# dremel.net
KiCad netlist of a schematic drawn in EAGLE
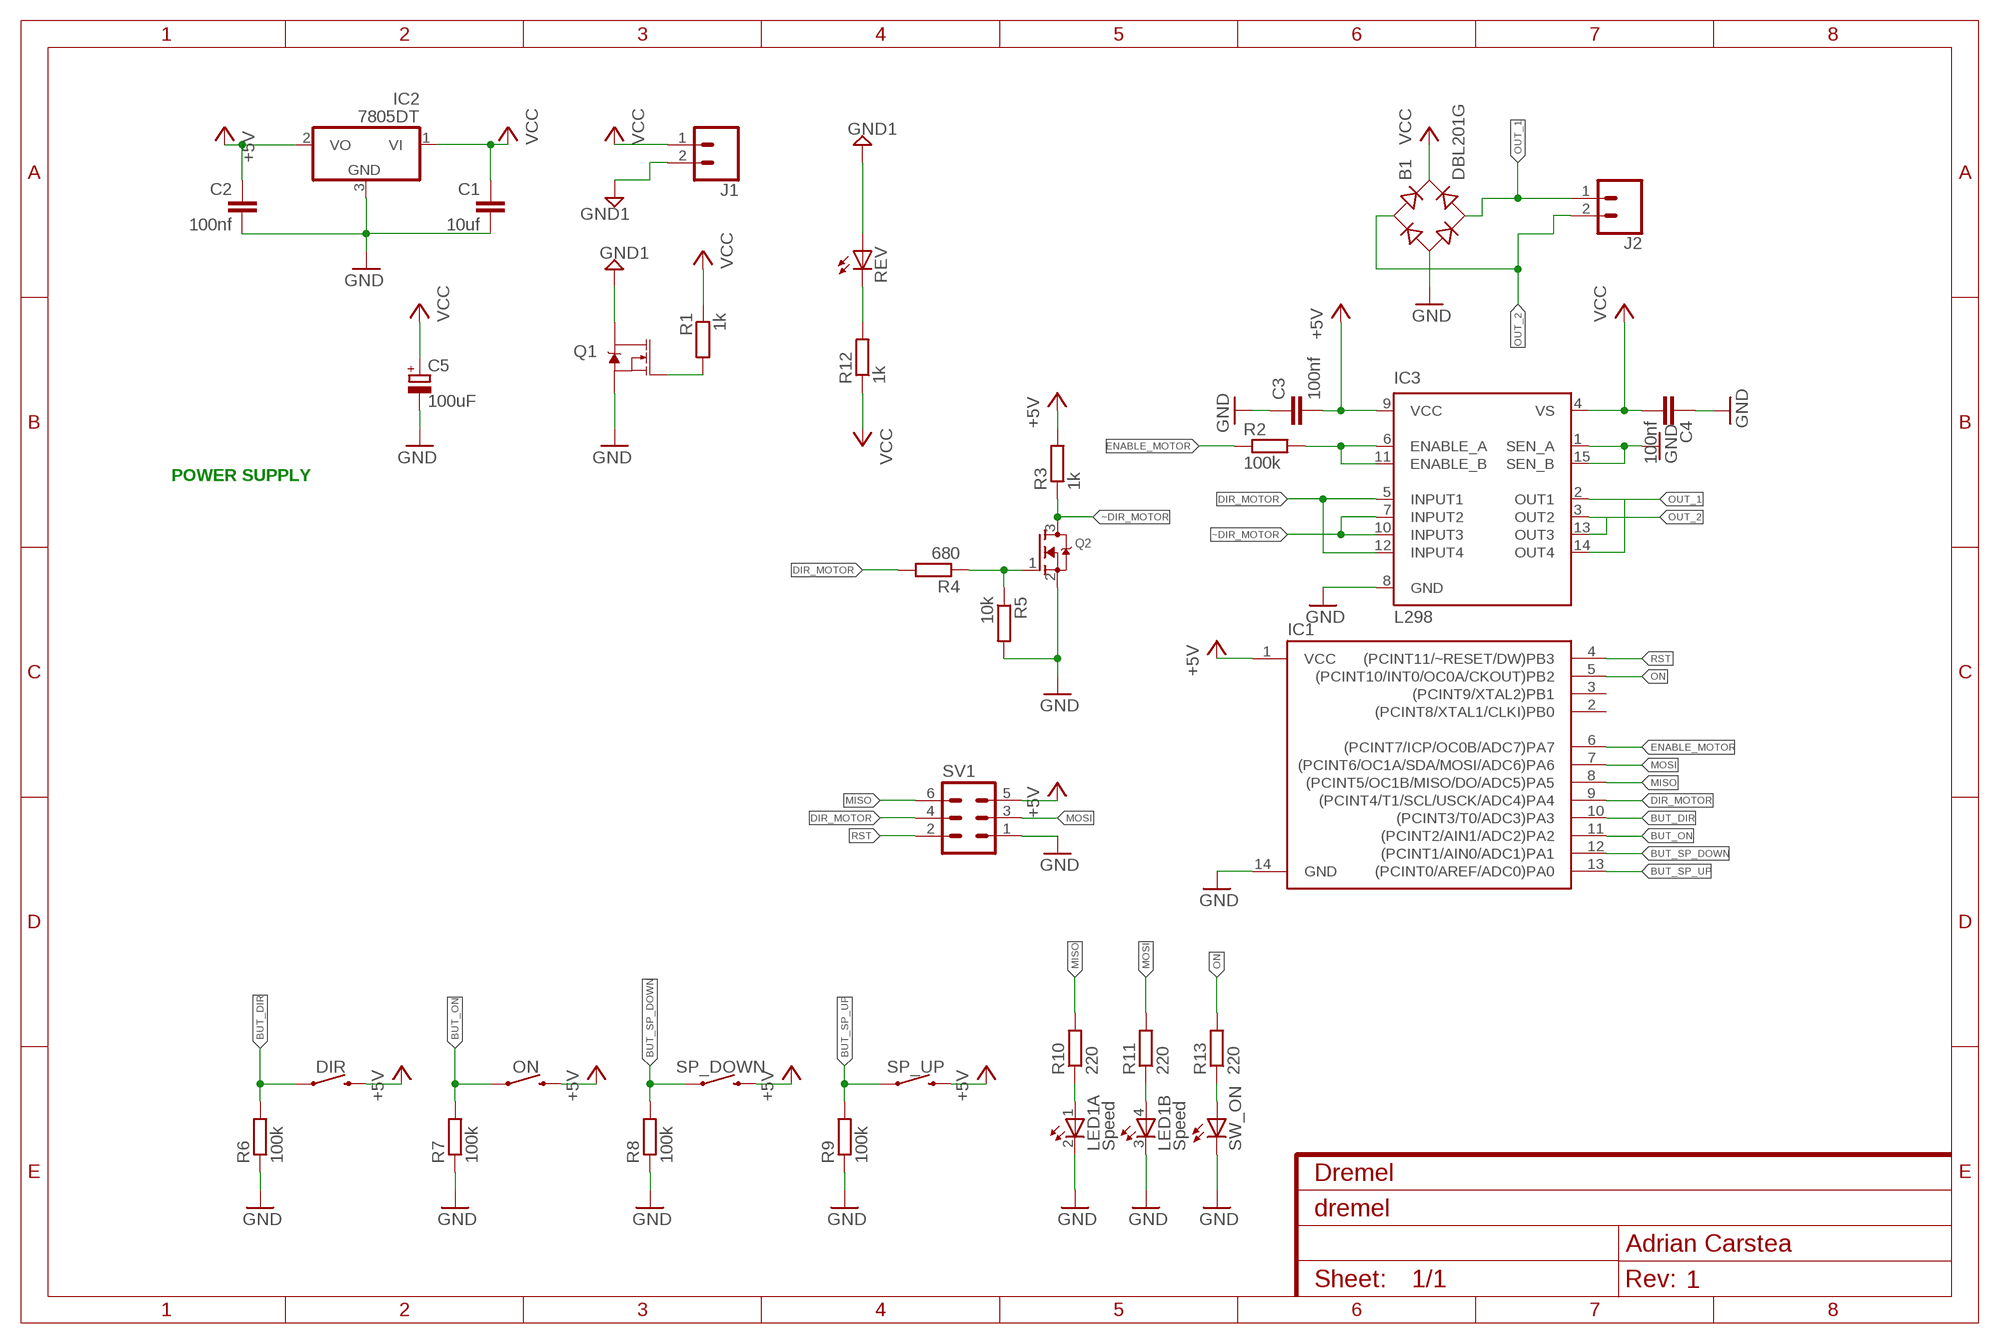
[diagram p0: schematic, sheet 1]

(export (version "E")
  (design (tool "Eeschema 10.0.6"))
  (components
    (comp (ref "B1")
      (value "DBL201G")
      (footprint "eagle-import:DB")
      (libsource (lib "eagle-import") (part "DB?GL201"))
    )
    (comp (ref "C1")
      (value "10uf")
      (footprint "eagle-import:C1206")
      (libsource (lib "eagle-import") (part "C-EUC1206"))
    )
    (comp (ref "C2")
      (value "100nf")
      (footprint "eagle-import:C1206")
      (libsource (lib "eagle-import") (part "C-EUC1206"))
    )
    (comp (ref "C3")
      (value "100nf")
      (footprint "eagle-import:C1206")
      (libsource (lib "eagle-import") (part "C-EUC1206"))
    )
    (comp (ref "C4")
      (value "100nf")
      (footprint "eagle-import:C1206")
      (libsource (lib "eagle-import") (part "C-EUC1206"))
    )
    (comp (ref "C5")
      (value "100uF")
      (footprint "eagle-import:E5-10,5")
      (libsource (lib "eagle-import") (part "CPOL-EUE5-10.5"))
    )
    (comp (ref "DIR")
      (value "MOMENTARY-SWITCH-SPST-SMD-5.2MM")
      (footprint "eagle-import:TACTILE_SWITCH_SMD_5.2MM")
      (libsource (lib "eagle-import") (part "MOMENTARY-SWITCH-SPST-SMD-5.2MM"))
    )
    (comp (ref "IC1")
      (value "ATTINY84ATTINY84-20PU")
      (footprint "eagle-import:DIP14")
      (libsource (lib "eagle-import") (part "ATTINY84ATTINY84-20PU"))
    )
    (comp (ref "IC2")
      (value "7805DT")
      (footprint "eagle-import:TO252")
      (libsource (lib "eagle-import") (part "78DT05"))
    )
    (comp (ref "IC3")
      (value "L298")
      (footprint "eagle-import:MULTIWATT-15")
      (fields (field (name "MPN") "L298N"))
      (libsource (lib "eagle-import") (part "L298"))
    )
    (comp (ref "J1")
      (value "CONN_025MM")
      (footprint "eagle-import:SCREWTERMINAL-5MM-2")
      (libsource (lib "eagle-import") (part "CONN_025MM"))
    )
    (comp (ref "J2")
      (value "CONN_025MM")
      (footprint "eagle-import:SCREWTERMINAL-5MM-2")
      (libsource (lib "eagle-import") (part "CONN_025MM"))
    )
    (comp (ref "LED1")
      (value "Speed")
      (footprint "eagle-import:P-LCC-4_2")
      (libsource (lib "eagle-import") (part "TOPLED-2-/"))
    )
    (comp (ref "ON")
      (value "MOMENTARY-SWITCH-SPST-SMD-5.2MM")
      (footprint "eagle-import:TACTILE_SWITCH_SMD_5.2MM")
      (libsource (lib "eagle-import") (part "MOMENTARY-SWITCH-SPST-SMD-5.2MM"))
    )
    (comp (ref "Q1")
      (value "MOSFET-NCH-FDD8780")
      (footprint "eagle-import:DPAK")
      (libsource (lib "eagle-import") (part "MOSFET-NCH-FDD8780"))
    )
    (comp (ref "Q2")
      (value "MOSFET-NREFLOW")
      (footprint "eagle-import:SOT23")
      (libsource (lib "eagle-import") (part "MOSFET-NREFLOW"))
    )
    (comp (ref "R1")
      (value "1k")
      (footprint "eagle-import:R0805")
      (libsource (lib "eagle-import") (part "R-EU_R0805"))
    )
    (comp (ref "R2")
      (value "100k")
      (footprint "eagle-import:M0805")
      (libsource (lib "eagle-import") (part "R-EU_M0805"))
    )
    (comp (ref "R3")
      (value "1k")
      (footprint "eagle-import:M0805")
      (libsource (lib "eagle-import") (part "R-EU_M0805"))
    )
    (comp (ref "R4")
      (value "680")
      (footprint "eagle-import:M0805")
      (libsource (lib "eagle-import") (part "R-EU_M0805"))
    )
    (comp (ref "R5")
      (value "10k")
      (footprint "eagle-import:M0805")
      (libsource (lib "eagle-import") (part "R-EU_M0805"))
    )
    (comp (ref "R6")
      (value "100k")
      (footprint "eagle-import:M0805")
      (libsource (lib "eagle-import") (part "R-EU_M0805"))
    )
    (comp (ref "R7")
      (value "100k")
      (footprint "eagle-import:M0805")
      (libsource (lib "eagle-import") (part "R-EU_M0805"))
    )
    (comp (ref "R8")
      (value "100k")
      (footprint "eagle-import:M0805")
      (libsource (lib "eagle-import") (part "R-EU_M0805"))
    )
    (comp (ref "R9")
      (value "100k")
      (footprint "eagle-import:M0805")
      (libsource (lib "eagle-import") (part "R-EU_M0805"))
    )
    (comp (ref "R10")
      (value "220")
      (footprint "eagle-import:M0805")
      (libsource (lib "eagle-import") (part "R-EU_M0805"))
    )
    (comp (ref "R11")
      (value "220")
      (footprint "eagle-import:M0805")
      (libsource (lib "eagle-import") (part "R-EU_M0805"))
    )
    (comp (ref "R12")
      (value "1k")
      (footprint "eagle-import:M0805")
      (libsource (lib "eagle-import") (part "R-EU_M0805"))
    )
    (comp (ref "R13")
      (value "220")
      (footprint "eagle-import:M0805")
      (libsource (lib "eagle-import") (part "R-EU_M0805"))
    )
    (comp (ref "REV")
      (value "LEDSML0805")
      (footprint "eagle-import:SML0805")
      (libsource (lib "eagle-import") (part "LEDSML0805"))
    )
    (comp (ref "SP_DOWN")
      (value "MOMENTARY-SWITCH-SPST-SMD-5.2MM")
      (footprint "eagle-import:TACTILE_SWITCH_SMD_5.2MM")
      (libsource (lib "eagle-import") (part "MOMENTARY-SWITCH-SPST-SMD-5.2MM"))
    )
    (comp (ref "SP_UP")
      (value "MOMENTARY-SWITCH-SPST-SMD-5.2MM")
      (footprint "eagle-import:TACTILE_SWITCH_SMD_5.2MM")
      (libsource (lib "eagle-import") (part "MOMENTARY-SWITCH-SPST-SMD-5.2MM"))
    )
    (comp (ref "SV1")
      (value "MA03-2")
      (footprint "eagle-import:MA03-2")
      (libsource (lib "eagle-import") (part "MA03-2"))
    )
    (comp (ref "SW_ON")
      (value "LEDSML0805")
      (footprint "eagle-import:SML0805")
      (libsource (lib "eagle-import") (part "LEDSML0805"))
    )
  )
  (nets
    (net (code "1") (name "+5V") (class "Default")
      (node (ref "C2") (pin "1") (pinfunction "1_1") (pintype "passive"))
      (node (ref "C3") (pin "2") (pinfunction "2_2") (pintype "passive"))
      (node (ref "DIR") (pin "3") (pinfunction "2_3") (pintype "passive"))
      (node (ref "IC1") (pin "1") (pinfunction "VCC_1") (pintype "bidirectional"))
      (node (ref "IC2") (pin "2") (pinfunction "VO_2") (pintype "passive"))
      (node (ref "IC3") (pin "9") (pinfunction "VCC_9") (pintype "power_in"))
      (node (ref "ON") (pin "3") (pinfunction "2_3") (pintype "passive"))
      (node (ref "R3") (pin "2") (pinfunction "2_2") (pintype "passive"))
      (node (ref "SP_DOWN") (pin "3") (pinfunction "2_3") (pintype "passive"))
      (node (ref "SP_UP") (pin "3") (pinfunction "2_3") (pintype "passive"))
      (node (ref "SV1") (pin "5") (pinfunction "5_5") (pintype "passive"))
    )
    (net (code "2") (name "/~{DIR_MOTOR}") (class "Default")
      (node (ref "IC3") (pin "10") (pinfunction "INPUT3_10") (pintype "input"))
      (node (ref "IC3") (pin "7") (pinfunction "INPUT2_7") (pintype "input"))
      (node (ref "Q2") (pin "3") (pinfunction "D_3") (pintype "bidirectional"))
      (node (ref "R3") (pin "1") (pinfunction "1_1") (pintype "passive"))
    )
    (net (code "3") (name "BUT_DIR") (class "Default")
      (node (ref "DIR") (pin "1") (pinfunction "1_1") (pintype "passive"))
      (node (ref "IC1") (pin "10") (pinfunction "(PCINT3/T0/ADC3)PA3_10") (pintype "bidirectional"))
      (node (ref "R6") (pin "2") (pinfunction "2_2") (pintype "passive"))
    )
    (net (code "4") (name "BUT_ON") (class "Default")
      (node (ref "IC1") (pin "11") (pinfunction "(PCINT2/AIN1/ADC2)PA2_11") (pintype "bidirectional"))
      (node (ref "ON") (pin "1") (pinfunction "1_1") (pintype "passive"))
      (node (ref "R7") (pin "2") (pinfunction "2_2") (pintype "passive"))
    )
    (net (code "5") (name "BUT_SP_DOWN") (class "Default")
      (node (ref "IC1") (pin "12") (pinfunction "(PCINT1/AIN0/ADC1)PA1_12") (pintype "bidirectional"))
      (node (ref "R8") (pin "2") (pinfunction "2_2") (pintype "passive"))
      (node (ref "SP_DOWN") (pin "1") (pinfunction "1_1") (pintype "passive"))
    )
    (net (code "6") (name "BUT_SP_UP") (class "Default")
      (node (ref "IC1") (pin "13") (pinfunction "(PCINT0/AREF/ADC0)PA0_13") (pintype "bidirectional"))
      (node (ref "R9") (pin "2") (pinfunction "2_2") (pintype "passive"))
      (node (ref "SP_UP") (pin "1") (pinfunction "1_1") (pintype "passive"))
    )
    (net (code "7") (name "DIR_MOTOR") (class "Default")
      (node (ref "IC1") (pin "9") (pinfunction "(PCINT4/T1/SCL/USCK/ADC4)PA4_9") (pintype "bidirectional"))
      (node (ref "IC3") (pin "12") (pinfunction "INPUT4_12") (pintype "input"))
      (node (ref "IC3") (pin "5") (pinfunction "INPUT1_5") (pintype "input"))
      (node (ref "R4") (pin "2") (pinfunction "2_2") (pintype "passive"))
      (node (ref "SV1") (pin "4") (pinfunction "4_4") (pintype "passive"))
    )
    (net (code "8") (name "ENABLE_MOTOR") (class "Default")
      (node (ref "IC1") (pin "6") (pinfunction "(PCINT7/ICP/OC0B/ADC7)PA7_6") (pintype "bidirectional"))
      (node (ref "R2") (pin "1") (pinfunction "1_1") (pintype "passive"))
    )
    (net (code "9") (name "GND") (class "Default")
      (node (ref "B1") (pin "-") (pinfunction "-_-") (pintype "passive"))
      (node (ref "C1") (pin "2") (pinfunction "2_2") (pintype "passive"))
      (node (ref "C2") (pin "2") (pinfunction "2_2") (pintype "passive"))
      (node (ref "C3") (pin "1") (pinfunction "1_1") (pintype "passive"))
      (node (ref "C4") (pin "1") (pinfunction "1_1") (pintype "passive"))
      (node (ref "C5") (pin "-") (pinfunction "-_-") (pintype "passive"))
      (node (ref "IC1") (pin "14") (pinfunction "GND_14") (pintype "bidirectional"))
      (node (ref "IC2") (pin "3") (pinfunction "GND_3") (pintype "passive"))
      (node (ref "IC3") (pin "1") (pinfunction "SEN_A_1") (pintype "input"))
      (node (ref "IC3") (pin "15") (pinfunction "SEN_B_15") (pintype "input"))
      (node (ref "IC3") (pin "8") (pinfunction "GND_8") (pintype "power_in"))
      (node (ref "LED1") (pin "2") (pinfunction "C_2") (pintype "passive"))
      (node (ref "LED1") (pin "3") (pinfunction "C_3") (pintype "passive"))
      (node (ref "Q1") (pin "3") (pinfunction "S_3") (pintype "bidirectional"))
      (node (ref "Q2") (pin "2") (pinfunction "S_2") (pintype "bidirectional"))
      (node (ref "R5") (pin "2") (pinfunction "2_2") (pintype "passive"))
      (node (ref "R6") (pin "1") (pinfunction "1_1") (pintype "passive"))
      (node (ref "R7") (pin "1") (pinfunction "1_1") (pintype "passive"))
      (node (ref "R8") (pin "1") (pinfunction "1_1") (pintype "passive"))
      (node (ref "R9") (pin "1") (pinfunction "1_1") (pintype "passive"))
      (node (ref "SV1") (pin "1") (pinfunction "1_1") (pintype "passive"))
      (node (ref "SW_ON") (pin "C") (pinfunction "C_C") (pintype "passive"))
    )
    (net (code "10") (name "GND1") (class "Default")
      (node (ref "J1") (pin "2") (pinfunction "2_2") (pintype "passive"))
      (node (ref "Q1") (pin "4") (pinfunction "D_4") (pintype "bidirectional"))
      (node (ref "REV") (pin "A") (pinfunction "A_A") (pintype "passive"))
    )
    (net (code "11") (name "MISO") (class "Default")
      (node (ref "IC1") (pin "8") (pinfunction "(PCINT5/OC1B/MISO/DO/ADC5)PA5_8") (pintype "bidirectional"))
      (node (ref "R10") (pin "2") (pinfunction "2_2") (pintype "passive"))
      (node (ref "SV1") (pin "6") (pinfunction "6_6") (pintype "passive"))
    )
    (net (code "12") (name "MOSI") (class "Default")
      (node (ref "IC1") (pin "7") (pinfunction "(PCINT6/OC1A/SDA/MOSI/ADC6)PA6_7") (pintype "bidirectional"))
      (node (ref "R11") (pin "2") (pinfunction "2_2") (pintype "passive"))
      (node (ref "SV1") (pin "3") (pinfunction "3_3") (pintype "passive"))
    )
    (net (code "13") (name "Net-(IC3-ENABLE_A)") (class "Default")
      (node (ref "IC3") (pin "11") (pinfunction "ENABLE_B_11") (pintype "input"))
      (node (ref "IC3") (pin "6") (pinfunction "ENABLE_A_6") (pintype "input"))
      (node (ref "R2") (pin "2") (pinfunction "2_2") (pintype "passive"))
    )
    (net (code "14") (name "Net-(LED1A-A)") (class "Default")
      (node (ref "LED1") (pin "1") (pinfunction "A_1") (pintype "passive"))
      (node (ref "R10") (pin "1") (pinfunction "1_1") (pintype "passive"))
    )
    (net (code "15") (name "Net-(LED1B-A)") (class "Default")
      (node (ref "LED1") (pin "4") (pinfunction "A_4") (pintype "passive"))
      (node (ref "R11") (pin "1") (pinfunction "1_1") (pintype "passive"))
    )
    (net (code "16") (name "Net-(Q1-G)") (class "Default")
      (node (ref "Q1") (pin "1") (pinfunction "G_1") (pintype "bidirectional"))
      (node (ref "R1") (pin "2") (pinfunction "2_2") (pintype "passive"))
    )
    (net (code "17") (name "Net-(Q2-G)") (class "Default")
      (node (ref "Q2") (pin "1") (pinfunction "G_1") (pintype "bidirectional"))
      (node (ref "R4") (pin "1") (pinfunction "1_1") (pintype "passive"))
      (node (ref "R5") (pin "1") (pinfunction "1_1") (pintype "passive"))
    )
    (net (code "18") (name "Net-(R12-Pad2)") (class "Default")
      (node (ref "R12") (pin "2") (pinfunction "2_2") (pintype "passive"))
      (node (ref "REV") (pin "C") (pinfunction "C_C") (pintype "passive"))
    )
    (net (code "19") (name "Net-(R13-Pad1)") (class "Default")
      (node (ref "R13") (pin "1") (pinfunction "1_1") (pintype "passive"))
      (node (ref "SW_ON") (pin "A") (pinfunction "A_A") (pintype "passive"))
    )
    (net (code "20") (name "ON") (class "Default")
      (node (ref "IC1") (pin "5") (pinfunction "(PCINT10/INT0/OC0A/CKOUT)PB2_5") (pintype "bidirectional"))
      (node (ref "R13") (pin "2") (pinfunction "2_2") (pintype "passive"))
    )
    (net (code "21") (name "OUT_1") (class "Default")
      (node (ref "B1") (pin "AC2") (pinfunction "AC2_AC2") (pintype "passive"))
      (node (ref "IC3") (pin "14") (pinfunction "OUT4_14") (pintype "output"))
      (node (ref "IC3") (pin "2") (pinfunction "OUT1_2") (pintype "output"))
      (node (ref "J2") (pin "1") (pinfunction "1_1") (pintype "passive"))
    )
    (net (code "22") (name "OUT_2") (class "Default")
      (node (ref "B1") (pin "AC1") (pinfunction "AC1_AC1") (pintype "passive"))
      (node (ref "IC3") (pin "13") (pinfunction "OUT3_13") (pintype "output"))
      (node (ref "IC3") (pin "3") (pinfunction "OUT2_3") (pintype "output"))
      (node (ref "J2") (pin "2") (pinfunction "2_2") (pintype "passive"))
    )
    (net (code "23") (name "RST") (class "Default")
      (node (ref "IC1") (pin "4") (pinfunction "(PCINT11/~{RESET/DW})PB3_4") (pintype "bidirectional"))
      (node (ref "SV1") (pin "2") (pinfunction "2_2") (pintype "passive"))
    )
    (net (code "24") (name "VCC") (class "Default")
      (node (ref "B1") (pin "+") (pinfunction "+_+") (pintype "passive"))
      (node (ref "C1") (pin "1") (pinfunction "1_1") (pintype "passive"))
      (node (ref "C4") (pin "2") (pinfunction "2_2") (pintype "passive"))
      (node (ref "C5") (pin "+") (pinfunction "+_+") (pintype "passive"))
      (node (ref "IC2") (pin "1") (pinfunction "VI_1") (pintype "input"))
      (node (ref "IC3") (pin "4") (pinfunction "VS_4") (pintype "power_in"))
      (node (ref "J1") (pin "1") (pinfunction "1_1") (pintype "passive"))
      (node (ref "R1") (pin "1") (pinfunction "1_1") (pintype "passive"))
      (node (ref "R12") (pin "1") (pinfunction "1_1") (pintype "passive"))
    )
    (net (code "25") (name "unconnected-(IC1-(PCINT8{slash}XTAL1{slash}CLKI)PB0-Pad2)") (class "Default")
      (node (ref "IC1") (pin "2") (pinfunction "(PCINT8/XTAL1/CLKI)PB0_2") (pintype "bidirectional"))
    )
    (net (code "26") (name "unconnected-(IC1-(PCINT9{slash}XTAL2)PB1-Pad3)") (class "Default")
      (node (ref "IC1") (pin "3") (pinfunction "(PCINT9/XTAL2)PB1_3") (pintype "bidirectional"))
    )
  )
)
